# MPU-6050_Breakout_V11.net
KiCad netlist of a schematic drawn in EAGLE
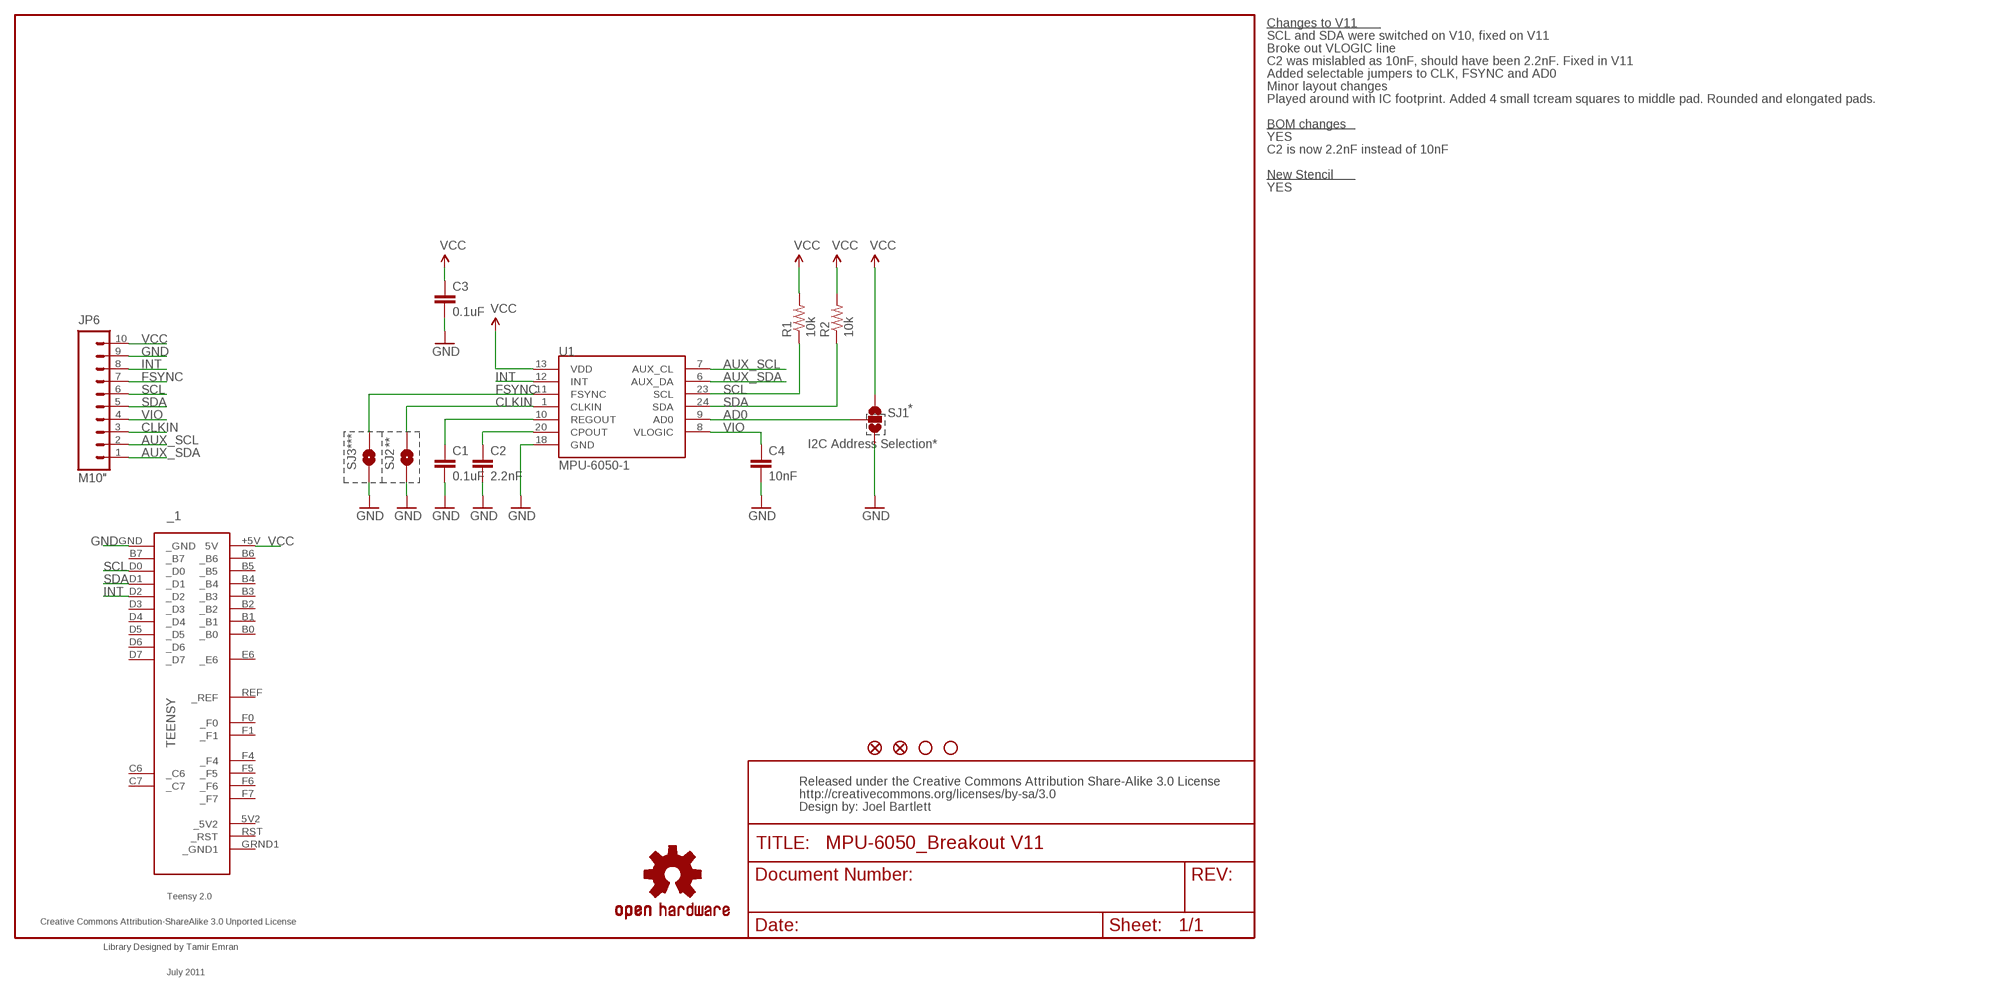
[diagram p0: schematic, sheet 1]

(export (version "E")
  (design (tool "Eeschema 10.0.6"))
  (components
    (comp (ref "C1")
      (value "0.1uF")
      (footprint "eagle-import:0402-CAP")
      (libsource (lib "eagle-import") (part "CAP0402-CAP"))
    )
    (comp (ref "C2")
      (value "2.2nF")
      (footprint "eagle-import:0402-CAP")
      (libsource (lib "eagle-import") (part "CAP0402-CAP"))
    )
    (comp (ref "C3")
      (value "0.1uF")
      (footprint "eagle-import:0402-CAP")
      (libsource (lib "eagle-import") (part "CAP0402-CAP"))
    )
    (comp (ref "C4")
      (value "10nF")
      (footprint "eagle-import:0402-CAP")
      (libsource (lib "eagle-import") (part "CAP0402-CAP"))
    )
    (comp (ref "JP2")
      (value "FIDUCIALUFIDUCIAL")
      (footprint "eagle-import:MICRO-FIDUCIAL")
      (libsource (lib "eagle-import") (part "FIDUCIALUFIDUCIAL"))
    )
    (comp (ref "JP3")
      (value "STAND-OFFTIGHT")
      (footprint "eagle-import:STAND-OFF-TIGHT")
      (libsource (lib "eagle-import") (part "STAND-OFFTIGHT"))
    )
    (comp (ref "JP4")
      (value "STAND-OFFTIGHT")
      (footprint "eagle-import:STAND-OFF-TIGHT")
      (libsource (lib "eagle-import") (part "STAND-OFFTIGHT"))
    )
    (comp (ref "JP5")
      (value "FIDUCIALUFIDUCIAL")
      (footprint "eagle-import:MICRO-FIDUCIAL")
      (libsource (lib "eagle-import") (part "FIDUCIALUFIDUCIAL"))
    )
    (comp (ref "JP6")
      (value "M10\"")
      (footprint "eagle-import:1X10")
      (libsource (lib "eagle-import") (part "M10{dblquote}"))
    )
    (comp (ref "R1")
      (value "10k")
      (footprint "eagle-import:0402-RES")
      (libsource (lib "eagle-import") (part "RESISTOR0402-RES"))
    )
    (comp (ref "R2")
      (value "10k")
      (footprint "eagle-import:0402-RES")
      (libsource (lib "eagle-import") (part "RESISTOR0402-RES"))
    )
    (comp (ref "SJ1")
      (value "SOLDERJUMPER_2WAYPASTE2&3")
      (footprint "eagle-import:SJ_3_PASTE2&3")
      (libsource (lib "eagle-import") (part "SOLDERJUMPER_2WAYPASTE2&3"))
    )
    (comp (ref "SJ2")
      (value "SOLDERJUMPERTRACE")
      (footprint "eagle-import:SJ_2S-TRACE")
      (libsource (lib "eagle-import") (part "SOLDERJUMPERTRACE"))
    )
    (comp (ref "SJ3")
      (value "SOLDERJUMPERTRACE")
      (footprint "eagle-import:SJ_2S-TRACE")
      (libsource (lib "eagle-import") (part "SOLDERJUMPERTRACE"))
    )
    (comp (ref "U$1")
      (value "OSHW-LOGOS")
      (footprint "eagle-import:OSHW-LOGO-S")
      (libsource (lib "eagle-import") (part "OSHW-LOGOS"))
    )
    (comp (ref "U1")
      (value "MPU-6050-1")
      (footprint "eagle-import:QFN-24-4MM2")
      (libsource (lib "eagle-import") (part "MPU-6050-1"))
    )
    (comp (ref "U3")
      (value "CREATIVE_COMMONS")
      (footprint "eagle-import:CREATIVE_COMMONS")
      (libsource (lib "eagle-import") (part "CREATIVE_COMMONS"))
    )
    (comp (ref "_1")
      (value "TEENSY")
      (footprint "eagle-import:TEENSY")
      (libsource (lib "eagle-import") (part "TEENSY"))
    )
  )
  (nets
    (net (code "1") (name "/AD0") (class "Default")
      (node (ref "SJ1") (pin "2") (pinfunction "2_2") (pintype "passive"))
      (node (ref "U1") (pin "9") (pinfunction "AD0_9") (pintype "bidirectional"))
    )
    (net (code "2") (name "/AUX_SCL") (class "Default")
      (node (ref "JP6") (pin "2") (pinfunction "2_2") (pintype "passive"))
      (node (ref "U1") (pin "7") (pinfunction "AUX_CL_7") (pintype "bidirectional"))
    )
    (net (code "3") (name "/AUX_SDA") (class "Default")
      (node (ref "JP6") (pin "1") (pinfunction "1_1") (pintype "passive"))
      (node (ref "U1") (pin "6") (pinfunction "AUX_DA_6") (pintype "bidirectional"))
    )
    (net (code "4") (name "/CLKIN") (class "Default")
      (node (ref "JP6") (pin "3") (pinfunction "3_3") (pintype "passive"))
      (node (ref "SJ2") (pin "2") (pinfunction "2_2") (pintype "passive"))
      (node (ref "U1") (pin "1") (pinfunction "CLKIN_1") (pintype "bidirectional"))
    )
    (net (code "5") (name "/FSYNC") (class "Default")
      (node (ref "JP6") (pin "7") (pinfunction "7_7") (pintype "passive"))
      (node (ref "SJ3") (pin "2") (pinfunction "2_2") (pintype "passive"))
      (node (ref "U1") (pin "11") (pinfunction "FSYNC_11") (pintype "bidirectional"))
    )
    (net (code "6") (name "/INT") (class "Default")
      (node (ref "JP6") (pin "8") (pinfunction "8_8") (pintype "passive"))
      (node (ref "U1") (pin "12") (pinfunction "INT_12") (pintype "bidirectional"))
      (node (ref "_1") (pin "D2") (pinfunction "_D2_D2") (pintype "bidirectional"))
    )
    (net (code "7") (name "/SCL") (class "Default")
      (node (ref "JP6") (pin "6") (pinfunction "6_6") (pintype "passive"))
      (node (ref "R1") (pin "1") (pinfunction "1_1") (pintype "passive"))
      (node (ref "U1") (pin "23") (pinfunction "SCL_23") (pintype "bidirectional"))
      (node (ref "_1") (pin "D0") (pinfunction "_D0_D0") (pintype "bidirectional"))
    )
    (net (code "8") (name "/SDA") (class "Default")
      (node (ref "JP6") (pin "5") (pinfunction "5_5") (pintype "passive"))
      (node (ref "R2") (pin "1") (pinfunction "1_1") (pintype "passive"))
      (node (ref "U1") (pin "24") (pinfunction "SDA_24") (pintype "bidirectional"))
      (node (ref "_1") (pin "D1") (pinfunction "_D1_D1") (pintype "bidirectional"))
    )
    (net (code "9") (name "/VIO") (class "Default")
      (node (ref "C4") (pin "1") (pinfunction "1_1") (pintype "passive"))
      (node (ref "JP6") (pin "4") (pinfunction "4_4") (pintype "passive"))
      (node (ref "U1") (pin "8") (pinfunction "VLOGIC_8") (pintype "bidirectional"))
    )
    (net (code "10") (name "GND") (class "Default")
      (node (ref "C1") (pin "2") (pinfunction "2_2") (pintype "passive"))
      (node (ref "C2") (pin "2") (pinfunction "2_2") (pintype "passive"))
      (node (ref "C3") (pin "2") (pinfunction "2_2") (pintype "passive"))
      (node (ref "C4") (pin "2") (pinfunction "2_2") (pintype "passive"))
      (node (ref "JP6") (pin "9") (pinfunction "9_9") (pintype "passive"))
      (node (ref "SJ1") (pin "3") (pinfunction "3_3") (pintype "passive"))
      (node (ref "SJ2") (pin "1") (pinfunction "1_1") (pintype "passive"))
      (node (ref "SJ3") (pin "1") (pinfunction "1_1") (pintype "passive"))
      (node (ref "U1") (pin "18") (pinfunction "GND_18") (pintype "bidirectional"))
      (node (ref "_1") (pin "GND") (pinfunction "_GND_GND") (pintype "bidirectional"))
    )
    (net (code "11") (name "Net-(U1-CPOUT)") (class "Default")
      (node (ref "C2") (pin "1") (pinfunction "1_1") (pintype "passive"))
      (node (ref "U1") (pin "20") (pinfunction "CPOUT_20") (pintype "bidirectional"))
    )
    (net (code "12") (name "Net-(U1-REGOUT)") (class "Default")
      (node (ref "C1") (pin "1") (pinfunction "1_1") (pintype "passive"))
      (node (ref "U1") (pin "10") (pinfunction "REGOUT_10") (pintype "bidirectional"))
    )
    (net (code "13") (name "VCC") (class "Default")
      (node (ref "C3") (pin "1") (pinfunction "1_1") (pintype "passive"))
      (node (ref "JP6") (pin "10") (pinfunction "10_10") (pintype "passive"))
      (node (ref "R1") (pin "2") (pinfunction "2_2") (pintype "passive"))
      (node (ref "R2") (pin "2") (pinfunction "2_2") (pintype "passive"))
      (node (ref "SJ1") (pin "1") (pinfunction "1_1") (pintype "passive"))
      (node (ref "U1") (pin "13") (pinfunction "VDD_13") (pintype "bidirectional"))
      (node (ref "_1") (pin "+5V") (pinfunction "5V_+5V") (pintype "bidirectional"))
    )
    (net (code "14") (name "unconnected-(_1-_5V2-Pad5V2)") (class "Default")
      (node (ref "_1") (pin "5V2") (pinfunction "_5V2_5V2") (pintype "bidirectional"))
    )
    (net (code "15") (name "unconnected-(_1-_B0-PadB0)") (class "Default")
      (node (ref "_1") (pin "B0") (pinfunction "_B0_B0") (pintype "bidirectional"))
    )
    (net (code "16") (name "unconnected-(_1-_B1-PadB1)") (class "Default")
      (node (ref "_1") (pin "B1") (pinfunction "_B1_B1") (pintype "bidirectional"))
    )
    (net (code "17") (name "unconnected-(_1-_B2-PadB2)") (class "Default")
      (node (ref "_1") (pin "B2") (pinfunction "_B2_B2") (pintype "bidirectional"))
    )
    (net (code "18") (name "unconnected-(_1-_B3-PadB3)") (class "Default")
      (node (ref "_1") (pin "B3") (pinfunction "_B3_B3") (pintype "bidirectional"))
    )
    (net (code "19") (name "unconnected-(_1-_B4-PadB4)") (class "Default")
      (node (ref "_1") (pin "B4") (pinfunction "_B4_B4") (pintype "bidirectional"))
    )
    (net (code "20") (name "unconnected-(_1-_B5-PadB5)") (class "Default")
      (node (ref "_1") (pin "B5") (pinfunction "_B5_B5") (pintype "bidirectional"))
    )
    (net (code "21") (name "unconnected-(_1-_B6-PadB6)") (class "Default")
      (node (ref "_1") (pin "B6") (pinfunction "_B6_B6") (pintype "bidirectional"))
    )
    (net (code "22") (name "unconnected-(_1-_B7-PadB7)") (class "Default")
      (node (ref "_1") (pin "B7") (pinfunction "_B7_B7") (pintype "bidirectional"))
    )
    (net (code "23") (name "unconnected-(_1-_C6-PadC6)") (class "Default")
      (node (ref "_1") (pin "C6") (pinfunction "_C6_C6") (pintype "bidirectional"))
    )
    (net (code "24") (name "unconnected-(_1-_C7-PadC7)") (class "Default")
      (node (ref "_1") (pin "C7") (pinfunction "_C7_C7") (pintype "bidirectional"))
    )
    (net (code "25") (name "unconnected-(_1-_D3-PadD3)") (class "Default")
      (node (ref "_1") (pin "D3") (pinfunction "_D3_D3") (pintype "bidirectional"))
    )
    (net (code "26") (name "unconnected-(_1-_D4-PadD4)") (class "Default")
      (node (ref "_1") (pin "D4") (pinfunction "_D4_D4") (pintype "bidirectional"))
    )
    (net (code "27") (name "unconnected-(_1-_D5-PadD5)") (class "Default")
      (node (ref "_1") (pin "D5") (pinfunction "_D5_D5") (pintype "bidirectional"))
    )
    (net (code "28") (name "unconnected-(_1-_D6-PadD6)") (class "Default")
      (node (ref "_1") (pin "D6") (pinfunction "_D6_D6") (pintype "bidirectional"))
    )
    (net (code "29") (name "unconnected-(_1-_D7-PadD7)") (class "Default")
      (node (ref "_1") (pin "D7") (pinfunction "_D7_D7") (pintype "bidirectional"))
    )
    (net (code "30") (name "unconnected-(_1-_E6-PadE6)") (class "Default")
      (node (ref "_1") (pin "E6") (pinfunction "_E6_E6") (pintype "bidirectional"))
    )
    (net (code "31") (name "unconnected-(_1-_F0-PadF0)") (class "Default")
      (node (ref "_1") (pin "F0") (pinfunction "_F0_F0") (pintype "bidirectional"))
    )
    (net (code "32") (name "unconnected-(_1-_F1-PadF1)") (class "Default")
      (node (ref "_1") (pin "F1") (pinfunction "_F1_F1") (pintype "bidirectional"))
    )
    (net (code "33") (name "unconnected-(_1-_F4-PadF4)") (class "Default")
      (node (ref "_1") (pin "F4") (pinfunction "_F4_F4") (pintype "bidirectional"))
    )
    (net (code "34") (name "unconnected-(_1-_F5-PadF5)") (class "Default")
      (node (ref "_1") (pin "F5") (pinfunction "_F5_F5") (pintype "bidirectional"))
    )
    (net (code "35") (name "unconnected-(_1-_F6-PadF6)") (class "Default")
      (node (ref "_1") (pin "F6") (pinfunction "_F6_F6") (pintype "bidirectional"))
    )
    (net (code "36") (name "unconnected-(_1-_F7-PadF7)") (class "Default")
      (node (ref "_1") (pin "F7") (pinfunction "_F7_F7") (pintype "bidirectional"))
    )
    (net (code "37") (name "unconnected-(_1-_GND1-PadGRND1)") (class "Default")
      (node (ref "_1") (pin "GRND1") (pinfunction "_GND1_GRND1") (pintype "bidirectional"))
    )
    (net (code "38") (name "unconnected-(_1-_REF-PadREF)") (class "Default")
      (node (ref "_1") (pin "REF") (pinfunction "_REF_REF") (pintype "bidirectional"))
    )
    (net (code "39") (name "unconnected-(_1-_RST-PadRST)") (class "Default")
      (node (ref "_1") (pin "RST") (pinfunction "_RST_RST") (pintype "bidirectional"))
    )
  )
)
